# LED_matrix.net
KiCad netlist of a schematic drawn in Altium Designer
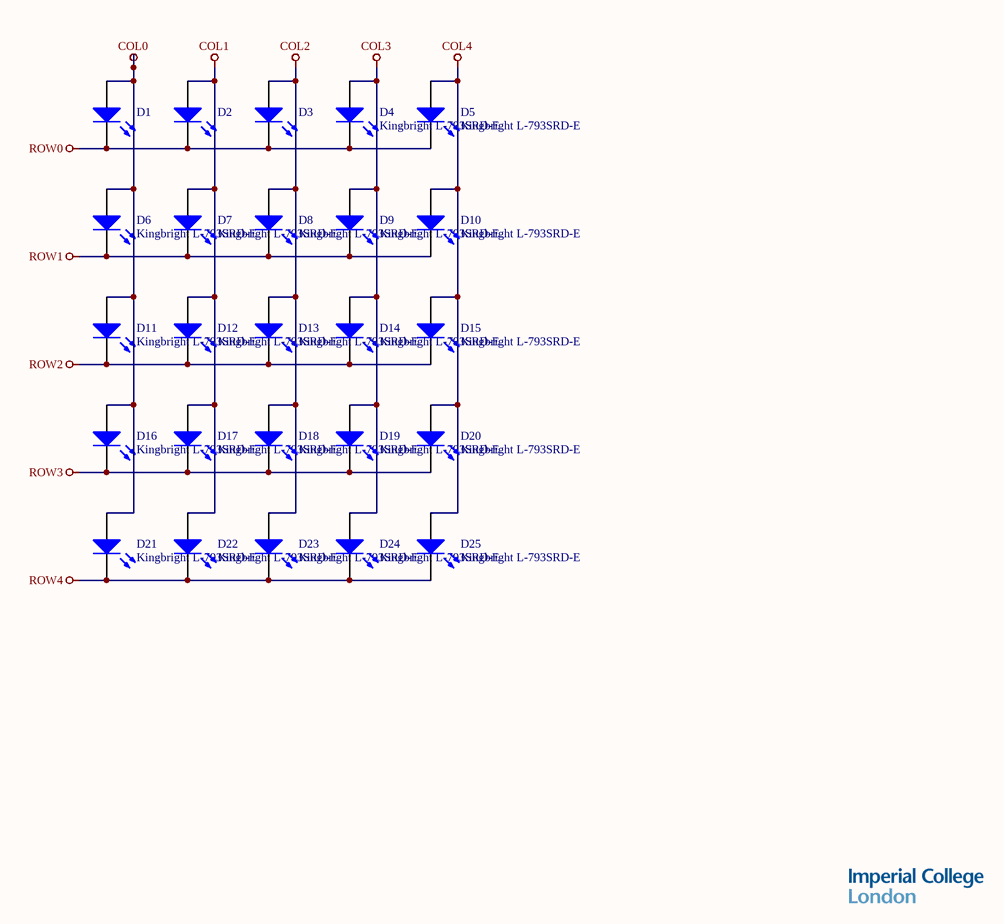
[diagram p0: LED matrix.SchDoc]

(export (version "E")
  (design (tool "Eeschema 10.0.6"))
  (components
    (comp (ref "D1")
      (value "Visual Communications VAOL-10GAT4")
      (footprint "PCB-lyzc1mpxh94ommceivxw-1")
      (description "Led, Red, t-3 (10mm), 480mcd, 640nm")
      (fields (field (name "MANUFACTURER PART NUMBER") "VAOL-10GAT4"))
      (libsource (lib "CommunityVault") (part "CMP-95e05c75ddf64a27-1"))
    )
    (comp (ref "D2")
      (value "Kingbright L-793SRD-E")
      (footprint "PCB-pjce6c538hbnjhyboevm-1")
      (description "L-793SRD-E, Round Series Red LED, 640 nm 8 mm, Round Lens Through Hole package")
      (libsource (lib "CommunityVault") (part "CMP-c7440e1cac271883-5"))
    )
    (comp (ref "D3")
      (value "Kingbright L-793SRD-E")
      (footprint "PCB-pjce6c538hbnjhyboevm-1")
      (description "L-793SRD-E, Round Series Red LED, 640 nm 8 mm, Round Lens Through Hole package")
      (libsource (lib "CommunityVault") (part "CMP-c7440e1cac271883-5"))
    )
    (comp (ref "D4")
      (value "Kingbright L-793SRD-E")
      (footprint "PCB-pjce6c538hbnjhyboevm-1")
      (description "L-793SRD-E, Round Series Red LED, 640 nm 8 mm, Round Lens Through Hole package")
      (libsource (lib "FavoritesLibrary") (part "SYM-c7440e1cac271883-1"))
    )
    (comp (ref "D5")
      (value "Kingbright L-793SRD-E")
      (footprint "PCB-pjce6c538hbnjhyboevm-1")
      (description "L-793SRD-E, Round Series Red LED, 640 nm 8 mm, Round Lens Through Hole package")
      (libsource (lib "FavoritesLibrary") (part "SYM-c7440e1cac271883-1"))
    )
    (comp (ref "D6")
      (value "Kingbright L-793SRD-E")
      (footprint "PCB-pjce6c538hbnjhyboevm-1")
      (description "L-793SRD-E, Round Series Red LED, 640 nm 8 mm, Round Lens Through Hole package")
      (libsource (lib "CommunityVault") (part "CMP-c7440e1cac271883-5"))
    )
    (comp (ref "D7")
      (value "Kingbright L-793SRD-E")
      (footprint "PCB-pjce6c538hbnjhyboevm-1")
      (description "L-793SRD-E, Round Series Red LED, 640 nm 8 mm, Round Lens Through Hole package")
      (libsource (lib "FavoritesLibrary") (part "SYM-c7440e1cac271883-1"))
    )
    (comp (ref "D8")
      (value "Kingbright L-793SRD-E")
      (footprint "PCB-pjce6c538hbnjhyboevm-1")
      (description "L-793SRD-E, Round Series Red LED, 640 nm 8 mm, Round Lens Through Hole package")
      (libsource (lib "FavoritesLibrary") (part "SYM-c7440e1cac271883-1"))
    )
    (comp (ref "D9")
      (value "Kingbright L-793SRD-E")
      (footprint "PCB-pjce6c538hbnjhyboevm-1")
      (description "L-793SRD-E, Round Series Red LED, 640 nm 8 mm, Round Lens Through Hole package")
      (libsource (lib "FavoritesLibrary") (part "SYM-c7440e1cac271883-1"))
    )
    (comp (ref "D10")
      (value "Kingbright L-793SRD-E")
      (footprint "PCB-pjce6c538hbnjhyboevm-1")
      (description "L-793SRD-E, Round Series Red LED, 640 nm 8 mm, Round Lens Through Hole package")
      (libsource (lib "FavoritesLibrary") (part "SYM-c7440e1cac271883-1"))
    )
    (comp (ref "D11")
      (value "Kingbright L-793SRD-E")
      (footprint "PCB-pjce6c538hbnjhyboevm-1")
      (description "L-793SRD-E, Round Series Red LED, 640 nm 8 mm, Round Lens Through Hole package")
      (libsource (lib "FavoritesLibrary") (part "SYM-c7440e1cac271883-1"))
    )
    (comp (ref "D12")
      (value "Kingbright L-793SRD-E")
      (footprint "PCB-pjce6c538hbnjhyboevm-1")
      (description "L-793SRD-E, Round Series Red LED, 640 nm 8 mm, Round Lens Through Hole package")
      (libsource (lib "FavoritesLibrary") (part "SYM-c7440e1cac271883-1"))
    )
    (comp (ref "D13")
      (value "Kingbright L-793SRD-E")
      (footprint "PCB-pjce6c538hbnjhyboevm-1")
      (description "L-793SRD-E, Round Series Red LED, 640 nm 8 mm, Round Lens Through Hole package")
      (libsource (lib "FavoritesLibrary") (part "SYM-c7440e1cac271883-1"))
    )
    (comp (ref "D14")
      (value "Kingbright L-793SRD-E")
      (footprint "PCB-pjce6c538hbnjhyboevm-1")
      (description "L-793SRD-E, Round Series Red LED, 640 nm 8 mm, Round Lens Through Hole package")
      (libsource (lib "FavoritesLibrary") (part "SYM-c7440e1cac271883-1"))
    )
    (comp (ref "D15")
      (value "Kingbright L-793SRD-E")
      (footprint "PCB-pjce6c538hbnjhyboevm-1")
      (description "L-793SRD-E, Round Series Red LED, 640 nm 8 mm, Round Lens Through Hole package")
      (libsource (lib "FavoritesLibrary") (part "SYM-c7440e1cac271883-1"))
    )
    (comp (ref "D16")
      (value "Kingbright L-793SRD-E")
      (footprint "PCB-pjce6c538hbnjhyboevm-1")
      (description "L-793SRD-E, Round Series Red LED, 640 nm 8 mm, Round Lens Through Hole package")
      (libsource (lib "FavoritesLibrary") (part "SYM-c7440e1cac271883-1"))
    )
    (comp (ref "D17")
      (value "Kingbright L-793SRD-E")
      (footprint "PCB-pjce6c538hbnjhyboevm-1")
      (description "L-793SRD-E, Round Series Red LED, 640 nm 8 mm, Round Lens Through Hole package")
      (libsource (lib "FavoritesLibrary") (part "SYM-c7440e1cac271883-1"))
    )
    (comp (ref "D18")
      (value "Kingbright L-793SRD-E")
      (footprint "PCB-pjce6c538hbnjhyboevm-1")
      (description "L-793SRD-E, Round Series Red LED, 640 nm 8 mm, Round Lens Through Hole package")
      (libsource (lib "FavoritesLibrary") (part "SYM-c7440e1cac271883-1"))
    )
    (comp (ref "D19")
      (value "Kingbright L-793SRD-E")
      (footprint "PCB-pjce6c538hbnjhyboevm-1")
      (description "L-793SRD-E, Round Series Red LED, 640 nm 8 mm, Round Lens Through Hole package")
      (libsource (lib "FavoritesLibrary") (part "SYM-c7440e1cac271883-1"))
    )
    (comp (ref "D20")
      (value "Kingbright L-793SRD-E")
      (footprint "PCB-pjce6c538hbnjhyboevm-1")
      (description "L-793SRD-E, Round Series Red LED, 640 nm 8 mm, Round Lens Through Hole package")
      (libsource (lib "FavoritesLibrary") (part "SYM-c7440e1cac271883-1"))
    )
    (comp (ref "D21")
      (value "Kingbright L-793SRD-E")
      (footprint "PCB-pjce6c538hbnjhyboevm-1")
      (description "L-793SRD-E, Round Series Red LED, 640 nm 8 mm, Round Lens Through Hole package")
      (libsource (lib "FavoritesLibrary") (part "SYM-c7440e1cac271883-1"))
    )
    (comp (ref "D22")
      (value "Kingbright L-793SRD-E")
      (footprint "PCB-pjce6c538hbnjhyboevm-1")
      (description "L-793SRD-E, Round Series Red LED, 640 nm 8 mm, Round Lens Through Hole package")
      (libsource (lib "FavoritesLibrary") (part "SYM-c7440e1cac271883-1"))
    )
    (comp (ref "D23")
      (value "Kingbright L-793SRD-E")
      (footprint "PCB-pjce6c538hbnjhyboevm-1")
      (description "L-793SRD-E, Round Series Red LED, 640 nm 8 mm, Round Lens Through Hole package")
      (libsource (lib "FavoritesLibrary") (part "SYM-c7440e1cac271883-1"))
    )
    (comp (ref "D24")
      (value "Kingbright L-793SRD-E")
      (footprint "PCB-pjce6c538hbnjhyboevm-1")
      (description "L-793SRD-E, Round Series Red LED, 640 nm 8 mm, Round Lens Through Hole package")
      (libsource (lib "FavoritesLibrary") (part "SYM-c7440e1cac271883-1"))
    )
    (comp (ref "D25")
      (value "Kingbright L-793SRD-E")
      (footprint "PCB-pjce6c538hbnjhyboevm-1")
      (description "L-793SRD-E, Round Series Red LED, 640 nm 8 mm, Round Lens Through Hole package")
      (libsource (lib "FavoritesLibrary") (part "SYM-c7440e1cac271883-1"))
    )
  )
  (nets
    (net (code "1") (name "COL0") (class "Default")
      (node (ref "D1") (pin "1") (pinfunction "A_1") (pintype "passive"))
      (node (ref "D11") (pin "1") (pinfunction "A_1") (pintype "passive"))
      (node (ref "D16") (pin "1") (pinfunction "A_1") (pintype "passive"))
      (node (ref "D21") (pin "1") (pinfunction "A_1") (pintype "passive"))
      (node (ref "D6") (pin "1") (pinfunction "A_1") (pintype "passive"))
    )
    (net (code "2") (name "COL1") (class "Default")
      (node (ref "D12") (pin "1") (pinfunction "A_1") (pintype "passive"))
      (node (ref "D17") (pin "1") (pinfunction "A_1") (pintype "passive"))
      (node (ref "D2") (pin "1") (pinfunction "A_1") (pintype "passive"))
      (node (ref "D22") (pin "1") (pinfunction "A_1") (pintype "passive"))
      (node (ref "D7") (pin "1") (pinfunction "A_1") (pintype "passive"))
    )
    (net (code "3") (name "COL2") (class "Default")
      (node (ref "D13") (pin "1") (pinfunction "A_1") (pintype "passive"))
      (node (ref "D18") (pin "1") (pinfunction "A_1") (pintype "passive"))
      (node (ref "D23") (pin "1") (pinfunction "A_1") (pintype "passive"))
      (node (ref "D3") (pin "1") (pinfunction "A_1") (pintype "passive"))
      (node (ref "D8") (pin "1") (pinfunction "A_1") (pintype "passive"))
    )
    (net (code "4") (name "COL3") (class "Default")
      (node (ref "D14") (pin "1") (pinfunction "A_1") (pintype "passive"))
      (node (ref "D19") (pin "1") (pinfunction "A_1") (pintype "passive"))
      (node (ref "D24") (pin "1") (pinfunction "A_1") (pintype "passive"))
      (node (ref "D4") (pin "1") (pinfunction "A_1") (pintype "passive"))
      (node (ref "D9") (pin "1") (pinfunction "A_1") (pintype "passive"))
    )
    (net (code "5") (name "COL4") (class "Default")
      (node (ref "D10") (pin "1") (pinfunction "A_1") (pintype "passive"))
      (node (ref "D15") (pin "1") (pinfunction "A_1") (pintype "passive"))
      (node (ref "D20") (pin "1") (pinfunction "A_1") (pintype "passive"))
      (node (ref "D25") (pin "1") (pinfunction "A_1") (pintype "passive"))
      (node (ref "D5") (pin "1") (pinfunction "A_1") (pintype "passive"))
    )
    (net (code "6") (name "ROW0") (class "Default")
      (node (ref "D1") (pin "2") (pinfunction "K_2") (pintype "passive"))
      (node (ref "D2") (pin "2") (pinfunction "K_2") (pintype "passive"))
      (node (ref "D3") (pin "2") (pinfunction "K_2") (pintype "passive"))
      (node (ref "D4") (pin "2") (pinfunction "K_2") (pintype "passive"))
      (node (ref "D5") (pin "2") (pinfunction "K_2") (pintype "passive"))
    )
    (net (code "7") (name "ROW1") (class "Default")
      (node (ref "D10") (pin "2") (pinfunction "K_2") (pintype "passive"))
      (node (ref "D6") (pin "2") (pinfunction "K_2") (pintype "passive"))
      (node (ref "D7") (pin "2") (pinfunction "K_2") (pintype "passive"))
      (node (ref "D8") (pin "2") (pinfunction "K_2") (pintype "passive"))
      (node (ref "D9") (pin "2") (pinfunction "K_2") (pintype "passive"))
    )
    (net (code "8") (name "ROW2") (class "Default")
      (node (ref "D11") (pin "2") (pinfunction "K_2") (pintype "passive"))
      (node (ref "D12") (pin "2") (pinfunction "K_2") (pintype "passive"))
      (node (ref "D13") (pin "2") (pinfunction "K_2") (pintype "passive"))
      (node (ref "D14") (pin "2") (pinfunction "K_2") (pintype "passive"))
      (node (ref "D15") (pin "2") (pinfunction "K_2") (pintype "passive"))
    )
    (net (code "9") (name "ROW3") (class "Default")
      (node (ref "D16") (pin "2") (pinfunction "K_2") (pintype "passive"))
      (node (ref "D17") (pin "2") (pinfunction "K_2") (pintype "passive"))
      (node (ref "D18") (pin "2") (pinfunction "K_2") (pintype "passive"))
      (node (ref "D19") (pin "2") (pinfunction "K_2") (pintype "passive"))
      (node (ref "D20") (pin "2") (pinfunction "K_2") (pintype "passive"))
    )
    (net (code "10") (name "ROW4") (class "Default")
      (node (ref "D21") (pin "2") (pinfunction "K_2") (pintype "passive"))
      (node (ref "D22") (pin "2") (pinfunction "K_2") (pintype "passive"))
      (node (ref "D23") (pin "2") (pinfunction "K_2") (pintype "passive"))
      (node (ref "D24") (pin "2") (pinfunction "K_2") (pintype "passive"))
      (node (ref "D25") (pin "2") (pinfunction "K_2") (pintype "passive"))
    )
  )
)
